# 10-Bit_RasPi-ADC_HAT_v21.net
KiCad netlist of a schematic drawn in EAGLE
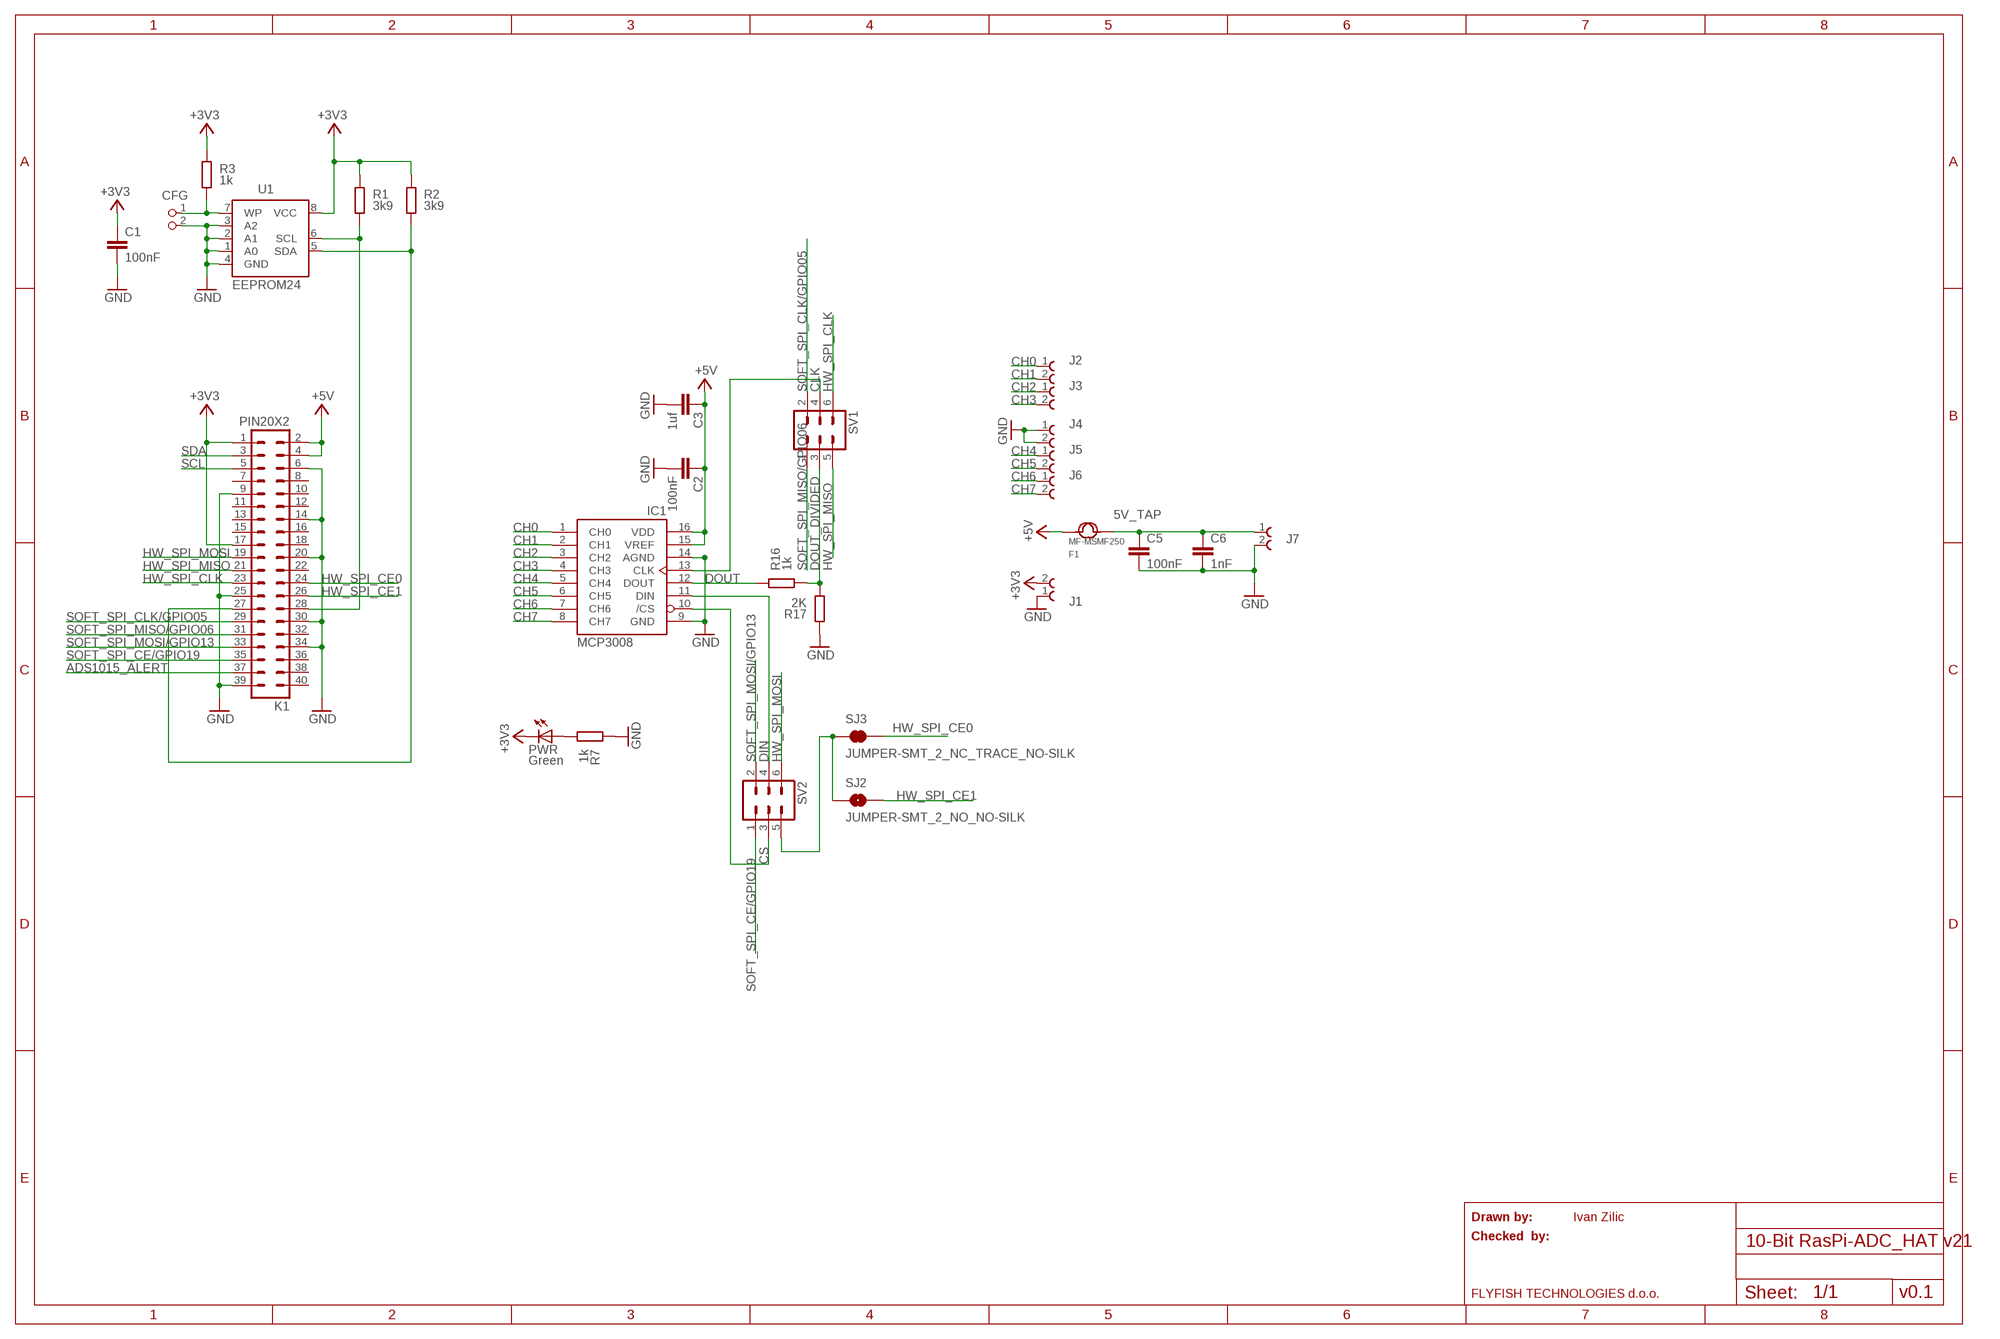
[diagram p0: schematic, sheet 1]

(export (version "E")
  (design (tool "Eeschema 10.0.6"))
  (components
    (comp (ref "C1")
      (value "100nF")
      (footprint "eagle-import:C0805K")
      (libsource (lib "eagle-import") (part "C-EUC0805K"))
    )
    (comp (ref "C2")
      (value "100nF")
      (footprint "eagle-import:C0805K")
      (libsource (lib "eagle-import") (part "C-EUC0805K"))
    )
    (comp (ref "C3")
      (value "1uf")
      (footprint "eagle-import:C0805K")
      (libsource (lib "eagle-import") (part "C-EUC0805K"))
    )
    (comp (ref "C5")
      (value "100nF")
      (footprint "eagle-import:C0805K")
      (libsource (lib "eagle-import") (part "C-EUC0805K"))
    )
    (comp (ref "C6")
      (value "1nF")
      (footprint "eagle-import:C0805K")
      (libsource (lib "eagle-import") (part "C-EUC0805K"))
    )
    (comp (ref "CFG")
      (value "PIN2_100")
      (footprint "eagle-import:PIN_W_2")
      (libsource (lib "eagle-import") (part "PIN2_100"))
    )
    (comp (ref "F1")
      (value "MF-MSMF250")
      (footprint "eagle-import:F1812")
      (fields (field (name "MPN") "MF-MSMF050-2"))
      (libsource (lib "eagle-import") (part "SMD-PPTC-USE-PPTC-0.50A-15V-0.15OHM(1812)"))
    )
    (comp (ref "IC1")
      (value "MCP3008")
      (footprint "eagle-import:DIL16")
      (libsource (lib "eagle-import") (part "MCP3008"))
    )
    (comp (ref "J1")
      (value "691214110002")
      (footprint "eagle-import:691214110002")
      (libsource (lib "eagle-import") (part "691214110002"))
    )
    (comp (ref "J2")
      (value "691214110002")
      (footprint "eagle-import:691214110002")
      (libsource (lib "eagle-import") (part "691214110002"))
    )
    (comp (ref "J3")
      (value "691214110002")
      (footprint "eagle-import:691214110002")
      (libsource (lib "eagle-import") (part "691214110002"))
    )
    (comp (ref "J4")
      (value "691214110002")
      (footprint "eagle-import:691214110002")
      (libsource (lib "eagle-import") (part "691214110002"))
    )
    (comp (ref "J5")
      (value "691214110002")
      (footprint "eagle-import:691214110002")
      (libsource (lib "eagle-import") (part "691214110002"))
    )
    (comp (ref "J6")
      (value "691214110002")
      (footprint "eagle-import:691214110002")
      (libsource (lib "eagle-import") (part "691214110002"))
    )
    (comp (ref "J7")
      (value "691214110002")
      (footprint "eagle-import:691214110002")
      (libsource (lib "eagle-import") (part "691214110002"))
    )
    (comp (ref "K1")
      (value "PIN20X2")
      (footprint "eagle-import:PIN_20X2")
      (libsource (lib "eagle-import") (part "PIN20X2"))
    )
    (comp (ref "PWR")
      (value "Green")
      (footprint "eagle-import:CHIPLED_0805")
      (libsource (lib "eagle-import") (part "LEDCHIPLED_0805"))
    )
    (comp (ref "R1")
      (value "3k9")
      (footprint "eagle-import:M0805")
      (fields (field (name "TOLERANCE") "5%"))
      (libsource (lib "eagle-import") (part "R-EU_M0805"))
    )
    (comp (ref "R2")
      (value "3k9")
      (footprint "eagle-import:M0805")
      (fields (field (name "TOLERANCE") "5%"))
      (libsource (lib "eagle-import") (part "R-EU_M0805"))
    )
    (comp (ref "R3")
      (value "1k")
      (footprint "eagle-import:M0805")
      (fields (field (name "TOLERANCE") "5%"))
      (libsource (lib "eagle-import") (part "R-EU_M0805"))
    )
    (comp (ref "R7")
      (value "1k")
      (footprint "eagle-import:M0805")
      (fields (field (name "TOLERANCE") "5%"))
      (libsource (lib "eagle-import") (part "R-EU_M0805"))
    )
    (comp (ref "R16")
      (value "1k")
      (footprint "eagle-import:M0805")
      (fields (field (name "TOLERANCE") "5%"))
      (libsource (lib "eagle-import") (part "R-EU_M0805"))
    )
    (comp (ref "R17")
      (value "2K")
      (footprint "eagle-import:M0805")
      (fields (field (name "TOLERANCE") "5%"))
      (libsource (lib "eagle-import") (part "R-EU_M0805"))
    )
    (comp (ref "SJ2")
      (value "JUMPER-SMT_2_NO_NO-SILK")
      (footprint "eagle-import:SMT-JUMPER_2_NO_NO-SILK")
      (libsource (lib "eagle-import") (part "JUMPER-SMT_2_NO_NO-SILK"))
    )
    (comp (ref "SJ3")
      (value "JUMPER-SMT_2_NC_TRACE_NO-SILK")
      (footprint "eagle-import:SMT-JUMPER_2_NC_TRACE_NO-SILK")
      (libsource (lib "eagle-import") (part "JUMPER-SMT_2_NC_TRACE_NO-SILK"))
    )
    (comp (ref "SV1")
      (value "MA03-2")
      (footprint "eagle-import:MA03-2")
      (libsource (lib "eagle-import") (part "MA03-2"))
    )
    (comp (ref "SV2")
      (value "MA03-2")
      (footprint "eagle-import:MA03-2")
      (libsource (lib "eagle-import") (part "MA03-2"))
    )
    (comp (ref "U1")
      (value "EEPROM24")
      (footprint "eagle-import:SOIC8")
      (libsource (lib "eagle-import") (part "EEPROM24"))
    )
  )
  (nets
    (net (code "1") (name "+3V3") (class "Default")
      (node (ref "C1") (pin "1") (pinfunction "1_1") (pintype "passive"))
      (node (ref "J1") (pin "2") (pinfunction "2_2") (pintype "passive"))
      (node (ref "K1") (pin "1") (pinfunction "1_1") (pintype "passive"))
      (node (ref "K1") (pin "17") (pinfunction "17_17") (pintype "passive"))
      (node (ref "PWR") (pin "C") (pinfunction "C_C") (pintype "passive"))
      (node (ref "R1") (pin "2") (pinfunction "2_2") (pintype "passive"))
      (node (ref "R2") (pin "2") (pinfunction "2_2") (pintype "passive"))
      (node (ref "R3") (pin "2") (pinfunction "2_2") (pintype "passive"))
      (node (ref "U1") (pin "8") (pinfunction "VCC_8") (pintype "power_in"))
    )
    (net (code "2") (name "+5V") (class "Default")
      (node (ref "C2") (pin "1") (pinfunction "1_1") (pintype "passive"))
      (node (ref "C3") (pin "1") (pinfunction "1_1") (pintype "passive"))
      (node (ref "F1") (pin "1") (pinfunction "1_1") (pintype "bidirectional"))
      (node (ref "IC1") (pin "15") (pinfunction "VREF_15") (pintype "input"))
      (node (ref "IC1") (pin "16") (pinfunction "VDD_16") (pintype "power_in"))
      (node (ref "K1") (pin "2") (pinfunction "2_2") (pintype "passive"))
      (node (ref "K1") (pin "4") (pinfunction "4_4") (pintype "passive"))
    )
    (net (code "3") (name "/5V_TAP") (class "Default")
      (node (ref "C5") (pin "1") (pinfunction "1_1") (pintype "passive"))
      (node (ref "C6") (pin "1") (pinfunction "1_1") (pintype "passive"))
      (node (ref "F1") (pin "2") (pinfunction "2_2") (pintype "bidirectional"))
      (node (ref "J7") (pin "1") (pinfunction "1_1") (pintype "passive"))
    )
    (net (code "4") (name "/ADS1015_ALERT") (class "Default")
      (node (ref "K1") (pin "37") (pinfunction "37_37") (pintype "passive"))
    )
    (net (code "5") (name "/CH0") (class "Default")
      (node (ref "IC1") (pin "1") (pinfunction "CH0_1") (pintype "input"))
      (node (ref "J2") (pin "1") (pinfunction "1_1") (pintype "passive"))
    )
    (net (code "6") (name "/CH1") (class "Default")
      (node (ref "IC1") (pin "2") (pinfunction "CH1_2") (pintype "input"))
      (node (ref "J2") (pin "2") (pinfunction "2_2") (pintype "passive"))
    )
    (net (code "7") (name "/CH2") (class "Default")
      (node (ref "IC1") (pin "3") (pinfunction "CH2_3") (pintype "input"))
      (node (ref "J3") (pin "1") (pinfunction "1_1") (pintype "passive"))
    )
    (net (code "8") (name "/CH3") (class "Default")
      (node (ref "IC1") (pin "4") (pinfunction "CH3_4") (pintype "input"))
      (node (ref "J3") (pin "2") (pinfunction "2_2") (pintype "passive"))
    )
    (net (code "9") (name "/CH4") (class "Default")
      (node (ref "IC1") (pin "5") (pinfunction "CH4_5") (pintype "input"))
      (node (ref "J5") (pin "1") (pinfunction "1_1") (pintype "passive"))
    )
    (net (code "10") (name "/CH5") (class "Default")
      (node (ref "IC1") (pin "6") (pinfunction "CH5_6") (pintype "input"))
      (node (ref "J5") (pin "2") (pinfunction "2_2") (pintype "passive"))
    )
    (net (code "11") (name "/CH6") (class "Default")
      (node (ref "IC1") (pin "7") (pinfunction "CH6_7") (pintype "input"))
      (node (ref "J6") (pin "1") (pinfunction "1_1") (pintype "passive"))
    )
    (net (code "12") (name "/CH7") (class "Default")
      (node (ref "IC1") (pin "8") (pinfunction "CH7_8") (pintype "input"))
      (node (ref "J6") (pin "2") (pinfunction "2_2") (pintype "passive"))
    )
    (net (code "13") (name "/CLK") (class "Default")
      (node (ref "IC1") (pin "13") (pinfunction "CLK_13") (pintype "input"))
      (node (ref "SV1") (pin "4") (pinfunction "4_4") (pintype "passive"))
    )
    (net (code "14") (name "/CS") (class "Default")
      (node (ref "IC1") (pin "10") (pinfunction "/CS_10") (pintype "input"))
      (node (ref "SV2") (pin "3") (pinfunction "3_3") (pintype "passive"))
    )
    (net (code "15") (name "/DIN") (class "Default")
      (node (ref "IC1") (pin "11") (pinfunction "DIN_11") (pintype "input"))
      (node (ref "SV2") (pin "4") (pinfunction "4_4") (pintype "passive"))
    )
    (net (code "16") (name "/DOUT") (class "Default")
      (node (ref "IC1") (pin "12") (pinfunction "DOUT_12") (pintype "output"))
      (node (ref "R16") (pin "2") (pinfunction "2_2") (pintype "passive"))
    )
    (net (code "17") (name "/DOUT_DIVIDED") (class "Default")
      (node (ref "R16") (pin "1") (pinfunction "1_1") (pintype "passive"))
      (node (ref "R17") (pin "1") (pinfunction "1_1") (pintype "passive"))
      (node (ref "SV1") (pin "3") (pinfunction "3_3") (pintype "passive"))
    )
    (net (code "18") (name "/HW_SPI_CE0") (class "Default")
      (node (ref "K1") (pin "24") (pinfunction "24_24") (pintype "passive"))
      (node (ref "SJ3") (pin "2") (pinfunction "2_2") (pintype "passive"))
    )
    (net (code "19") (name "/HW_SPI_CE1") (class "Default")
      (node (ref "K1") (pin "26") (pinfunction "26_26") (pintype "passive"))
      (node (ref "SJ2") (pin "2") (pinfunction "2_2") (pintype "passive"))
    )
    (net (code "20") (name "/HW_SPI_CLK") (class "Default")
      (node (ref "K1") (pin "23") (pinfunction "23_23") (pintype "passive"))
      (node (ref "SV1") (pin "6") (pinfunction "6_6") (pintype "passive"))
    )
    (net (code "21") (name "/HW_SPI_MISO") (class "Default")
      (node (ref "K1") (pin "21") (pinfunction "21_21") (pintype "passive"))
      (node (ref "SV1") (pin "5") (pinfunction "5_5") (pintype "passive"))
    )
    (net (code "22") (name "/HW_SPI_MOSI") (class "Default")
      (node (ref "K1") (pin "19") (pinfunction "19_19") (pintype "passive"))
      (node (ref "SV2") (pin "6") (pinfunction "6_6") (pintype "passive"))
    )
    (net (code "23") (name "/SCL") (class "Default")
      (node (ref "K1") (pin "5") (pinfunction "5_5") (pintype "passive"))
    )
    (net (code "24") (name "/SDA") (class "Default")
      (node (ref "K1") (pin "3") (pinfunction "3_3") (pintype "passive"))
    )
    (net (code "25") (name "/SOFT_SPI_CE{slash}GPIO19") (class "Default")
      (node (ref "K1") (pin "35") (pinfunction "35_35") (pintype "passive"))
      (node (ref "SV2") (pin "1") (pinfunction "1_1") (pintype "passive"))
    )
    (net (code "26") (name "/SOFT_SPI_CLK{slash}GPIO05") (class "Default")
      (node (ref "K1") (pin "29") (pinfunction "29_29") (pintype "passive"))
      (node (ref "SV1") (pin "2") (pinfunction "2_2") (pintype "passive"))
    )
    (net (code "27") (name "/SOFT_SPI_MISO{slash}GPIO06") (class "Default")
      (node (ref "K1") (pin "31") (pinfunction "31_31") (pintype "passive"))
      (node (ref "SV1") (pin "1") (pinfunction "1_1") (pintype "passive"))
    )
    (net (code "28") (name "/SOFT_SPI_MOSI{slash}GPIO13") (class "Default")
      (node (ref "K1") (pin "33") (pinfunction "33_33") (pintype "passive"))
      (node (ref "SV2") (pin "2") (pinfunction "2_2") (pintype "passive"))
    )
    (net (code "29") (name "GND") (class "Default")
      (node (ref "C1") (pin "2") (pinfunction "2_2") (pintype "passive"))
      (node (ref "C2") (pin "2") (pinfunction "2_2") (pintype "passive"))
      (node (ref "C3") (pin "2") (pinfunction "2_2") (pintype "passive"))
      (node (ref "C5") (pin "2") (pinfunction "2_2") (pintype "passive"))
      (node (ref "C6") (pin "2") (pinfunction "2_2") (pintype "passive"))
      (node (ref "CFG") (pin "2") (pinfunction "2_2") (pintype "passive"))
      (node (ref "IC1") (pin "14") (pinfunction "AGND_14") (pintype "power_in"))
      (node (ref "IC1") (pin "9") (pinfunction "GND_9") (pintype "power_in"))
      (node (ref "J1") (pin "1") (pinfunction "1_1") (pintype "passive"))
      (node (ref "J4") (pin "1") (pinfunction "1_1") (pintype "passive"))
      (node (ref "J4") (pin "2") (pinfunction "2_2") (pintype "passive"))
      (node (ref "J7") (pin "2") (pinfunction "2_2") (pintype "passive"))
      (node (ref "K1") (pin "14") (pinfunction "14_14") (pintype "passive"))
      (node (ref "K1") (pin "20") (pinfunction "20_20") (pintype "passive"))
      (node (ref "K1") (pin "25") (pinfunction "25_25") (pintype "passive"))
      (node (ref "K1") (pin "30") (pinfunction "30_30") (pintype "passive"))
      (node (ref "K1") (pin "34") (pinfunction "34_34") (pintype "passive"))
      (node (ref "K1") (pin "39") (pinfunction "39_39") (pintype "passive"))
      (node (ref "K1") (pin "6") (pinfunction "6_6") (pintype "passive"))
      (node (ref "K1") (pin "9") (pinfunction "9_9") (pintype "passive"))
      (node (ref "R17") (pin "2") (pinfunction "2_2") (pintype "passive"))
      (node (ref "R7") (pin "2") (pinfunction "2_2") (pintype "passive"))
      (node (ref "U1") (pin "1") (pinfunction "A0_1") (pintype "input"))
      (node (ref "U1") (pin "2") (pinfunction "A1_2") (pintype "input"))
      (node (ref "U1") (pin "3") (pinfunction "A2_3") (pintype "input"))
      (node (ref "U1") (pin "4") (pinfunction "GND_4") (pintype "power_in"))
    )
    (net (code "30") (name "Net-(PWR-PadA)") (class "Default")
      (node (ref "PWR") (pin "A") (pinfunction "A_A") (pintype "passive"))
      (node (ref "R7") (pin "1") (pinfunction "1_1") (pintype "passive"))
    )
    (net (code "31") (name "Net-(SJ2-Pad1)") (class "Default")
      (node (ref "SJ2") (pin "1") (pinfunction "1_1") (pintype "passive"))
      (node (ref "SJ3") (pin "1") (pinfunction "1_1") (pintype "passive"))
      (node (ref "SV2") (pin "5") (pinfunction "5_5") (pintype "passive"))
    )
    (net (code "32") (name "Net-(U1-SCL)") (class "Default")
      (node (ref "K1") (pin "28") (pinfunction "28_28") (pintype "passive"))
      (node (ref "R1") (pin "1") (pinfunction "1_1") (pintype "passive"))
      (node (ref "U1") (pin "6") (pinfunction "SCL_6") (pintype "input"))
    )
    (net (code "33") (name "Net-(U1-SDA)") (class "Default")
      (node (ref "K1") (pin "27") (pinfunction "27_27") (pintype "passive"))
      (node (ref "R2") (pin "1") (pinfunction "1_1") (pintype "passive"))
      (node (ref "U1") (pin "5") (pinfunction "SDA_5") (pintype "bidirectional"))
    )
    (net (code "34") (name "Net-(U1-WP)") (class "Default")
      (node (ref "CFG") (pin "1") (pinfunction "1_1") (pintype "passive"))
      (node (ref "R3") (pin "1") (pinfunction "1_1") (pintype "passive"))
      (node (ref "U1") (pin "7") (pinfunction "WP_7") (pintype "input"))
    )
    (net (code "35") (name "unconnected-(K1-Pad7)") (class "Default")
      (node (ref "K1") (pin "7") (pinfunction "7_7") (pintype "passive"))
    )
    (net (code "36") (name "unconnected-(K1-Pad8)") (class "Default")
      (node (ref "K1") (pin "8") (pinfunction "8_8") (pintype "passive"))
    )
    (net (code "37") (name "unconnected-(K1-Pad10)") (class "Default")
      (node (ref "K1") (pin "10") (pinfunction "10_10") (pintype "passive"))
    )
    (net (code "38") (name "unconnected-(K1-Pad11)") (class "Default")
      (node (ref "K1") (pin "11") (pinfunction "11_11") (pintype "passive"))
    )
    (net (code "39") (name "unconnected-(K1-Pad12)") (class "Default")
      (node (ref "K1") (pin "12") (pinfunction "12_12") (pintype "passive"))
    )
    (net (code "40") (name "unconnected-(K1-Pad13)") (class "Default")
      (node (ref "K1") (pin "13") (pinfunction "13_13") (pintype "passive"))
    )
    (net (code "41") (name "unconnected-(K1-Pad15)") (class "Default")
      (node (ref "K1") (pin "15") (pinfunction "15_15") (pintype "passive"))
    )
    (net (code "42") (name "unconnected-(K1-Pad16)") (class "Default")
      (node (ref "K1") (pin "16") (pinfunction "16_16") (pintype "passive"))
    )
    (net (code "43") (name "unconnected-(K1-Pad18)") (class "Default")
      (node (ref "K1") (pin "18") (pinfunction "18_18") (pintype "passive"))
    )
    (net (code "44") (name "unconnected-(K1-Pad22)") (class "Default")
      (node (ref "K1") (pin "22") (pinfunction "22_22") (pintype "passive"))
    )
    (net (code "45") (name "unconnected-(K1-Pad32)") (class "Default")
      (node (ref "K1") (pin "32") (pinfunction "32_32") (pintype "passive"))
    )
    (net (code "46") (name "unconnected-(K1-Pad36)") (class "Default")
      (node (ref "K1") (pin "36") (pinfunction "36_36") (pintype "passive"))
    )
    (net (code "47") (name "unconnected-(K1-Pad38)") (class "Default")
      (node (ref "K1") (pin "38") (pinfunction "38_38") (pintype "passive"))
    )
    (net (code "48") (name "unconnected-(K1-Pad40)") (class "Default")
      (node (ref "K1") (pin "40") (pinfunction "40_40") (pintype "passive"))
    )
  )
)
